# 780-00059revA_-_SCH_Sinistro_Camera_Cont.net
KiCad netlist of a schematic drawn in Altium Designer
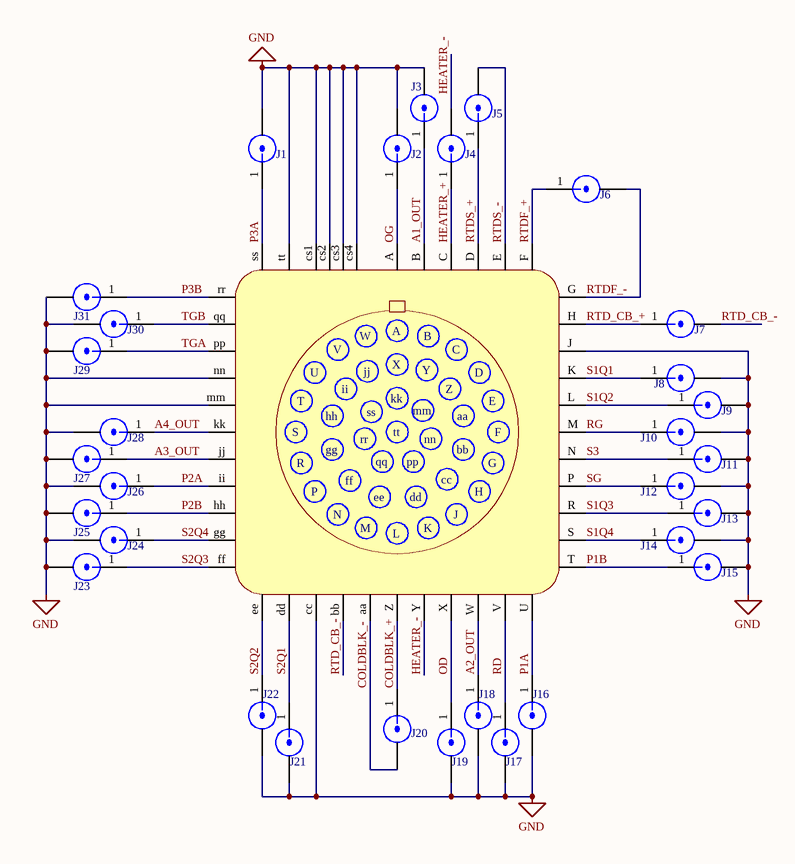
[diagram p0: 780-00059revA - SCH, Sinistro Camera Controller Extension.SchDoc]

(export (version "E")
  (design (tool "Eeschema 10.0.6"))
  (components
    (comp (ref "J1")
      (value "RG-178_CoaxTermination")
      (footprint "RG-178_TERMINATION")
      (description "Coax termination")
      (libsource (lib "ImagingLabLibrary") (part "RG-178_CoaxTermination"))
    )
    (comp (ref "J2")
      (value "RG-178_CoaxTermination")
      (footprint "RG-178_TERMINATION")
      (libsource (lib "ImagingLabLibrary") (part "RG-178_CoaxTermination"))
    )
    (comp (ref "J3")
      (value "RG-178_CoaxTermination")
      (footprint "RG-178_TERMINATION")
      (libsource (lib "ImagingLabLibrary") (part "RG-178_CoaxTermination"))
    )
    (comp (ref "J4")
      (value "RG-178_CoaxTermination")
      (footprint "RG-178_TERMINATION")
      (libsource (lib "ImagingLabLibrary") (part "RG-178_CoaxTermination"))
    )
    (comp (ref "J5")
      (value "RG-178_CoaxTermination")
      (footprint "RG-178_TERMINATION")
      (libsource (lib "ImagingLabLibrary") (part "RG-178_CoaxTermination"))
    )
    (comp (ref "J6")
      (value "RG-178_CoaxTermination")
      (footprint "RG-178_TERMINATION")
      (libsource (lib "ImagingLabLibrary") (part "RG-178_CoaxTermination"))
    )
    (comp (ref "J7")
      (value "RG-178_CoaxTermination")
      (footprint "RG-178_TERMINATION")
      (libsource (lib "ImagingLabLibrary") (part "RG-178_CoaxTermination"))
    )
    (comp (ref "J8")
      (value "RG-178_CoaxTermination")
      (footprint "RG-178_TERMINATION")
      (libsource (lib "ImagingLabLibrary") (part "RG-178_CoaxTermination"))
    )
    (comp (ref "J9")
      (value "RG-178_CoaxTermination")
      (footprint "RG-178_TERMINATION")
      (libsource (lib "ImagingLabLibrary") (part "RG-178_CoaxTermination"))
    )
    (comp (ref "J10")
      (value "RG-178_CoaxTermination")
      (footprint "RG-178_TERMINATION")
      (libsource (lib "ImagingLabLibrary") (part "RG-178_CoaxTermination"))
    )
    (comp (ref "J11")
      (value "RG-178_CoaxTermination")
      (footprint "RG-178_TERMINATION")
      (libsource (lib "ImagingLabLibrary") (part "RG-178_CoaxTermination"))
    )
    (comp (ref "J12")
      (value "RG-178_CoaxTermination")
      (footprint "RG-178_TERMINATION")
      (libsource (lib "ImagingLabLibrary") (part "RG-178_CoaxTermination"))
    )
    (comp (ref "J13")
      (value "RG-178_CoaxTermination")
      (footprint "RG-178_TERMINATION")
      (libsource (lib "ImagingLabLibrary") (part "RG-178_CoaxTermination"))
    )
    (comp (ref "J14")
      (value "RG-178_CoaxTermination")
      (footprint "RG-178_TERMINATION")
      (libsource (lib "ImagingLabLibrary") (part "RG-178_CoaxTermination"))
    )
    (comp (ref "J15")
      (value "RG-178_CoaxTermination")
      (footprint "RG-178_TERMINATION")
      (libsource (lib "ImagingLabLibrary") (part "RG-178_CoaxTermination"))
    )
    (comp (ref "J16")
      (value "RG-178_CoaxTermination")
      (footprint "RG-178_TERMINATION")
      (libsource (lib "ImagingLabLibrary") (part "RG-178_CoaxTermination"))
    )
    (comp (ref "J17")
      (value "RG-178_CoaxTermination")
      (footprint "RG-178_TERMINATION")
      (libsource (lib "ImagingLabLibrary") (part "RG-178_CoaxTermination"))
    )
    (comp (ref "J18")
      (value "RG-178_CoaxTermination")
      (footprint "RG-178_TERMINATION")
      (libsource (lib "ImagingLabLibrary") (part "RG-178_CoaxTermination"))
    )
    (comp (ref "J19")
      (value "RG-178_CoaxTermination")
      (footprint "RG-178_TERMINATION")
      (libsource (lib "ImagingLabLibrary") (part "RG-178_CoaxTermination"))
    )
    (comp (ref "J20")
      (value "RG-178_CoaxTermination")
      (footprint "RG-178_TERMINATION")
      (libsource (lib "ImagingLabLibrary") (part "RG-178_CoaxTermination"))
    )
    (comp (ref "J21")
      (value "RG-178_CoaxTermination")
      (footprint "RG-178_TERMINATION")
      (libsource (lib "ImagingLabLibrary") (part "RG-178_CoaxTermination"))
    )
    (comp (ref "J22")
      (value "RG-178_CoaxTermination")
      (footprint "RG-178_TERMINATION")
      (libsource (lib "ImagingLabLibrary") (part "RG-178_CoaxTermination"))
    )
    (comp (ref "J23")
      (value "RG-178_CoaxTermination")
      (footprint "RG-178_TERMINATION")
      (libsource (lib "ImagingLabLibrary") (part "RG-178_CoaxTermination"))
    )
    (comp (ref "J24")
      (value "RG-178_CoaxTermination")
      (footprint "RG-178_TERMINATION")
      (libsource (lib "ImagingLabLibrary") (part "RG-178_CoaxTermination"))
    )
    (comp (ref "J25")
      (value "RG-178_CoaxTermination")
      (footprint "RG-178_TERMINATION")
      (libsource (lib "ImagingLabLibrary") (part "RG-178_CoaxTermination"))
    )
    (comp (ref "J26")
      (value "RG-178_CoaxTermination")
      (footprint "RG-178_TERMINATION")
      (libsource (lib "ImagingLabLibrary") (part "RG-178_CoaxTermination"))
    )
    (comp (ref "J27")
      (value "RG-178_CoaxTermination")
      (footprint "RG-178_TERMINATION")
      (libsource (lib "ImagingLabLibrary") (part "RG-178_CoaxTermination"))
    )
    (comp (ref "J28")
      (value "RG-178_CoaxTermination")
      (footprint "RG-178_TERMINATION")
      (libsource (lib "ImagingLabLibrary") (part "RG-178_CoaxTermination"))
    )
    (comp (ref "J29")
      (value "RG-178_CoaxTermination")
      (footprint "RG-178_TERMINATION")
      (libsource (lib "ImagingLabLibrary") (part "RG-178_CoaxTermination"))
    )
    (comp (ref "J30")
      (value "RG-178_CoaxTermination")
      (footprint "RG-178_TERMINATION")
      (libsource (lib "ImagingLabLibrary") (part "RG-178_CoaxTermination"))
    )
    (comp (ref "J31")
      (value "RG-178_CoaxTermination")
      (footprint "RG-178_TERMINATION")
      (libsource (lib "ImagingLabLibrary") (part "RG-178_CoaxTermination"))
    )
    (comp (ref "P1")
      (value "125-00409 - MIL-DTL-26482 20-41 Pins, Jam nut")
      (footprint "MS-3116 Size 20-41, Male")
      (libsource (lib "ImagingLabLibrary") (part "125-00409 - MIL-DTL-26482 20-41 Pins, Jam nut"))
    )
  )
  (nets
    (net (code "1") (name "/A1_OUT") (class "Default")
      (node (ref "J3") (pin "1") (pinfunction "1_1") (pintype "passive"))
      (node (ref "P1") (pin "B") (pinfunction "B_B") (pintype "passive"))
    )
    (net (code "2") (name "/A2_OUT") (class "Default")
      (node (ref "J18") (pin "1") (pinfunction "1_1") (pintype "passive"))
      (node (ref "P1") (pin "W") (pinfunction "W_W") (pintype "passive"))
    )
    (net (code "3") (name "/A3_OUT") (class "Default")
      (node (ref "J27") (pin "1") (pinfunction "1_1") (pintype "passive"))
      (node (ref "P1") (pin "jj") (pinfunction "jj_jj") (pintype "passive"))
    )
    (net (code "4") (name "/A4_OUT") (class "Default")
      (node (ref "J28") (pin "1") (pinfunction "1_1") (pintype "passive"))
      (node (ref "P1") (pin "kk") (pinfunction "kk_kk") (pintype "passive"))
    )
    (net (code "5") (name "/COLDBLK_+") (class "Default")
      (node (ref "J20") (pin "1") (pinfunction "1_1") (pintype "passive"))
      (node (ref "P1") (pin "Z") (pinfunction "Z_Z") (pintype "passive"))
    )
    (net (code "6") (name "/COLDBLK_-") (class "Default")
      (node (ref "J20") (pin "GND") (pinfunction "GND_GND") (pintype "passive"))
      (node (ref "P1") (pin "aa") (pinfunction "aa_aa") (pintype "passive"))
    )
    (net (code "7") (name "/HEATER_+") (class "Default")
      (node (ref "J4") (pin "1") (pinfunction "1_1") (pintype "passive"))
      (node (ref "P1") (pin "C") (pinfunction "C_C") (pintype "passive"))
    )
    (net (code "8") (name "/HEATER_-") (class "Default")
      (node (ref "J4") (pin "GND") (pinfunction "GND_GND") (pintype "passive"))
      (node (ref "P1") (pin "Y") (pinfunction "Y_Y") (pintype "passive"))
    )
    (net (code "9") (name "/OD") (class "Default")
      (node (ref "J19") (pin "1") (pinfunction "1_1") (pintype "passive"))
      (node (ref "P1") (pin "X") (pinfunction "X_X") (pintype "passive"))
    )
    (net (code "10") (name "/OG") (class "Default")
      (node (ref "J2") (pin "1") (pinfunction "1_1") (pintype "passive"))
      (node (ref "P1") (pin "A") (pinfunction "A_A") (pintype "passive"))
    )
    (net (code "11") (name "/P1A") (class "Default")
      (node (ref "J16") (pin "1") (pinfunction "1_1") (pintype "passive"))
      (node (ref "P1") (pin "U") (pinfunction "U_U") (pintype "passive"))
    )
    (net (code "12") (name "/P1B") (class "Default")
      (node (ref "J15") (pin "1") (pinfunction "1_1") (pintype "passive"))
      (node (ref "P1") (pin "T") (pinfunction "T_T") (pintype "passive"))
    )
    (net (code "13") (name "/P2A") (class "Default")
      (node (ref "J26") (pin "1") (pinfunction "1_1") (pintype "passive"))
      (node (ref "P1") (pin "ii") (pinfunction "ii_ii") (pintype "passive"))
    )
    (net (code "14") (name "/P2B") (class "Default")
      (node (ref "J25") (pin "1") (pinfunction "1_1") (pintype "passive"))
      (node (ref "P1") (pin "hh") (pinfunction "hh_hh") (pintype "passive"))
    )
    (net (code "15") (name "/P3A") (class "Default")
      (node (ref "J1") (pin "1") (pinfunction "1_1") (pintype "passive"))
      (node (ref "P1") (pin "ss") (pinfunction "ss_ss") (pintype "passive"))
    )
    (net (code "16") (name "/P3B") (class "Default")
      (node (ref "J31") (pin "1") (pinfunction "1_1") (pintype "passive"))
      (node (ref "P1") (pin "rr") (pinfunction "rr_rr") (pintype "passive"))
    )
    (net (code "17") (name "/RD") (class "Default")
      (node (ref "J17") (pin "1") (pinfunction "1_1") (pintype "passive"))
      (node (ref "P1") (pin "V") (pinfunction "V_V") (pintype "passive"))
    )
    (net (code "18") (name "/RG") (class "Default")
      (node (ref "J10") (pin "1") (pinfunction "1_1") (pintype "passive"))
      (node (ref "P1") (pin "M") (pinfunction "M_M") (pintype "passive"))
    )
    (net (code "19") (name "/RTDF_+") (class "Default")
      (node (ref "J6") (pin "1") (pinfunction "1_1") (pintype "passive"))
      (node (ref "P1") (pin "F") (pinfunction "F_F") (pintype "passive"))
    )
    (net (code "20") (name "/RTDF_-") (class "Default")
      (node (ref "J6") (pin "GND") (pinfunction "GND_GND") (pintype "passive"))
      (node (ref "P1") (pin "G") (pinfunction "G_G") (pintype "passive"))
    )
    (net (code "21") (name "/RTDS_+") (class "Default")
      (node (ref "J5") (pin "1") (pinfunction "1_1") (pintype "passive"))
      (node (ref "P1") (pin "D") (pinfunction "D_D") (pintype "passive"))
    )
    (net (code "22") (name "/RTDS_-") (class "Default")
      (node (ref "J5") (pin "GND") (pinfunction "GND_GND") (pintype "passive"))
      (node (ref "P1") (pin "E") (pinfunction "E_E") (pintype "passive"))
    )
    (net (code "23") (name "/RTD_CB_+") (class "Default")
      (node (ref "J7") (pin "1") (pinfunction "1_1") (pintype "passive"))
      (node (ref "P1") (pin "H") (pinfunction "H_H") (pintype "passive"))
    )
    (net (code "24") (name "/RTD_CB_-") (class "Default")
      (node (ref "J7") (pin "GND") (pinfunction "GND_GND") (pintype "passive"))
      (node (ref "P1") (pin "bb") (pinfunction "bb_bb") (pintype "passive"))
    )
    (net (code "25") (name "/S1Q1") (class "Default")
      (node (ref "J8") (pin "1") (pinfunction "1_1") (pintype "passive"))
      (node (ref "P1") (pin "K") (pinfunction "K_K") (pintype "passive"))
    )
    (net (code "26") (name "/S1Q2") (class "Default")
      (node (ref "J9") (pin "1") (pinfunction "1_1") (pintype "passive"))
      (node (ref "P1") (pin "L") (pinfunction "L_L") (pintype "passive"))
    )
    (net (code "27") (name "/S1Q3") (class "Default")
      (node (ref "J13") (pin "1") (pinfunction "1_1") (pintype "passive"))
      (node (ref "P1") (pin "R") (pinfunction "R_R") (pintype "passive"))
    )
    (net (code "28") (name "/S1Q4") (class "Default")
      (node (ref "J14") (pin "1") (pinfunction "1_1") (pintype "passive"))
      (node (ref "P1") (pin "S") (pinfunction "S_S") (pintype "passive"))
    )
    (net (code "29") (name "/S2Q1") (class "Default")
      (node (ref "J21") (pin "1") (pinfunction "1_1") (pintype "passive"))
      (node (ref "P1") (pin "dd") (pinfunction "dd_dd") (pintype "passive"))
    )
    (net (code "30") (name "/S2Q2") (class "Default")
      (node (ref "J22") (pin "1") (pinfunction "1_1") (pintype "passive"))
      (node (ref "P1") (pin "ee") (pinfunction "ee_ee") (pintype "passive"))
    )
    (net (code "31") (name "/S2Q3") (class "Default")
      (node (ref "J23") (pin "1") (pinfunction "1_1") (pintype "passive"))
      (node (ref "P1") (pin "ff") (pinfunction "ff_ff") (pintype "passive"))
    )
    (net (code "32") (name "/S2Q4") (class "Default")
      (node (ref "J24") (pin "1") (pinfunction "1_1") (pintype "passive"))
      (node (ref "P1") (pin "gg") (pinfunction "gg_gg") (pintype "passive"))
    )
    (net (code "33") (name "/S3") (class "Default")
      (node (ref "J11") (pin "1") (pinfunction "1_1") (pintype "passive"))
      (node (ref "P1") (pin "N") (pinfunction "N_N") (pintype "passive"))
    )
    (net (code "34") (name "/SG") (class "Default")
      (node (ref "J12") (pin "1") (pinfunction "1_1") (pintype "passive"))
      (node (ref "P1") (pin "P") (pinfunction "P_P") (pintype "passive"))
    )
    (net (code "35") (name "/TGA") (class "Default")
      (node (ref "J29") (pin "1") (pinfunction "1_1") (pintype "passive"))
      (node (ref "P1") (pin "pp") (pinfunction "pp_pp") (pintype "passive"))
    )
    (net (code "36") (name "/TGB") (class "Default")
      (node (ref "J30") (pin "1") (pinfunction "1_1") (pintype "passive"))
      (node (ref "P1") (pin "qq") (pinfunction "qq_qq") (pintype "passive"))
    )
    (net (code "37") (name "GND") (class "Default")
      (node (ref "J1") (pin "GND") (pinfunction "GND_GND") (pintype "passive"))
      (node (ref "J10") (pin "GND") (pinfunction "GND_GND") (pintype "passive"))
      (node (ref "J11") (pin "GND") (pinfunction "GND_GND") (pintype "passive"))
      (node (ref "J12") (pin "GND") (pinfunction "GND_GND") (pintype "passive"))
      (node (ref "J13") (pin "GND") (pinfunction "GND_GND") (pintype "passive"))
      (node (ref "J14") (pin "GND") (pinfunction "GND_GND") (pintype "passive"))
      (node (ref "J15") (pin "GND") (pinfunction "GND_GND") (pintype "passive"))
      (node (ref "J16") (pin "GND") (pinfunction "GND_GND") (pintype "passive"))
      (node (ref "J17") (pin "GND") (pinfunction "GND_GND") (pintype "passive"))
      (node (ref "J18") (pin "GND") (pinfunction "GND_GND") (pintype "passive"))
      (node (ref "J19") (pin "GND") (pinfunction "GND_GND") (pintype "passive"))
      (node (ref "J2") (pin "GND") (pinfunction "GND_GND") (pintype "passive"))
      (node (ref "J21") (pin "GND") (pinfunction "GND_GND") (pintype "passive"))
      (node (ref "J22") (pin "GND") (pinfunction "GND_GND") (pintype "passive"))
      (node (ref "J23") (pin "GND") (pinfunction "GND_GND") (pintype "passive"))
      (node (ref "J24") (pin "GND") (pinfunction "GND_GND") (pintype "passive"))
      (node (ref "J25") (pin "GND") (pinfunction "GND_GND") (pintype "passive"))
      (node (ref "J26") (pin "GND") (pinfunction "GND_GND") (pintype "passive"))
      (node (ref "J27") (pin "GND") (pinfunction "GND_GND") (pintype "passive"))
      (node (ref "J28") (pin "GND") (pinfunction "GND_GND") (pintype "passive"))
      (node (ref "J29") (pin "GND") (pinfunction "GND_GND") (pintype "passive"))
      (node (ref "J3") (pin "GND") (pinfunction "GND_GND") (pintype "passive"))
      (node (ref "J30") (pin "GND") (pinfunction "GND_GND") (pintype "passive"))
      (node (ref "J31") (pin "GND") (pinfunction "GND_GND") (pintype "passive"))
      (node (ref "J8") (pin "GND") (pinfunction "GND_GND") (pintype "passive"))
      (node (ref "J9") (pin "GND") (pinfunction "GND_GND") (pintype "passive"))
      (node (ref "P1") (pin "J") (pinfunction "J_J") (pintype "passive"))
      (node (ref "P1") (pin "cc") (pinfunction "cc_cc") (pintype "passive"))
      (node (ref "P1") (pin "cs1") (pinfunction "cs1_cs1") (pintype "passive"))
      (node (ref "P1") (pin "cs2") (pinfunction "cs2_cs2") (pintype "passive"))
      (node (ref "P1") (pin "cs3") (pinfunction "cs3_cs3") (pintype "passive"))
      (node (ref "P1") (pin "cs4") (pinfunction "cs4_cs4") (pintype "passive"))
      (node (ref "P1") (pin "mm") (pinfunction "mm_mm") (pintype "passive"))
      (node (ref "P1") (pin "nn") (pinfunction "nn_nn") (pintype "passive"))
      (node (ref "P1") (pin "tt") (pinfunction "tt_tt") (pintype "passive"))
    )
  )
)
